# Snap2.net
KiCad netlist of a schematic drawn in Altium Designer
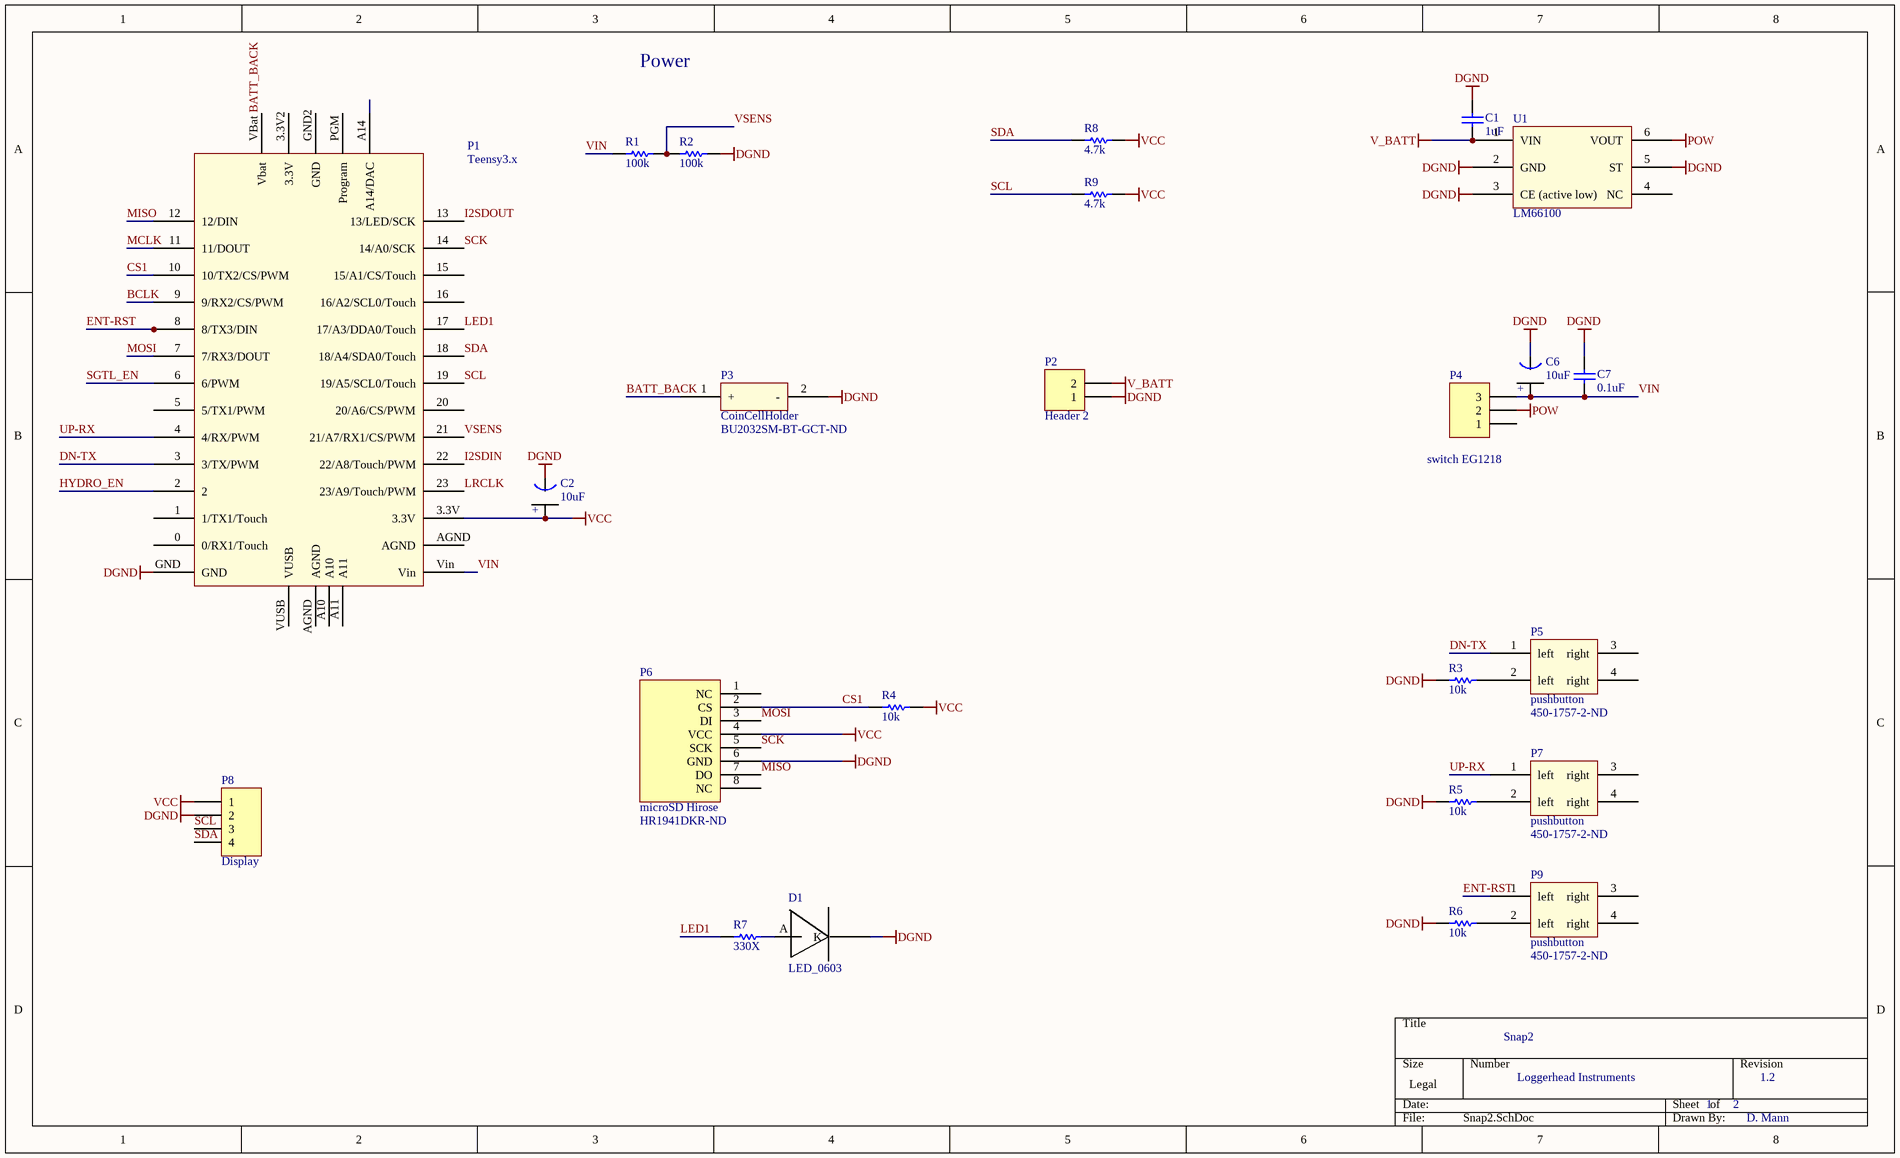
[diagram p0: Snap2.SchDoc]

(export (version "E")
  (design (tool "Eeschema 10.0.6"))
  (components
    (comp (ref "C1")
      (value "1uF")
      (footprint "0402")
      (description "Ceramic Chip Capacitor - Standard")
      (fields (field (name "PUBLISHER") "Altium Limited"))
      (libsource (lib "KEMET Chip Capacitor") (part "C0402"))
    )
    (comp (ref "C2") (value "10uF") (footprint "Tant0805") (libsource (lib "Loggerhead") (part "Tant0805")))
    (comp (ref "C6") (value "10uF") (footprint "Tant0805") (libsource (lib "Loggerhead") (part "Tant0805")))
    (comp (ref "C7")
      (value "0.1uF")
      (footprint "0402")
      (description "Ceramic Chip Capacitor - Standard")
      (fields (field (name "PUBLISHER") "Altium Limited"))
      (libsource (lib "KEMET Chip Capacitor") (part "C0402"))
    )
    (comp (ref "D1")
      (value "LED_0603")
      (footprint "Diode0603")
      (libsource (lib "Loggerhead") (part "LED_0603"))
    )
    (comp (ref "P1")
      (value "Teensy3.x")
      (footprint "Teensy3.x")
      (libsource (lib "Teensy") (part "Teensy3.x"))
    )
    (comp (ref "P2")
      (value "Header 2")
      (footprint "HDR1X2")
      (description "Header, 2-Pin")
      (fields (field (name "PUBLISHER") "Altium Limited"))
      (libsource (lib "Miscellaneous Connectors") (part "Header 2"))
    )
    (comp (ref "P3")
      (value "CoinCellHolder")
      (footprint "CoinCellHolder")
      (fields (field (name "SUPPLIER PART NUMBER 1") "BU2032SM-BT-GCT-ND"))
      (libsource (lib "Loggerhead") (part "CoinCellHolder"))
    )
    (comp (ref "P4")
      (value "switch EG1218")
      (footprint "HDR1X3")
      (description "Header, 3-Pin")
      (fields (field (name "PUBLISHER") "Altium Limited"))
      (libsource (lib "Miscellaneous Connectors") (part "Header 3"))
    )
    (comp (ref "P5")
      (value "pushbutton")
      (footprint "SOP4")
      (fields (field (name "SUPPLIER PART NUMBER 1") "450-1757-2-ND"))
      (libsource (lib "Loggerhead") (part "pushbutton"))
    )
    (comp (ref "P6")
      (value "microSD Hirose")
      (footprint "DM3D microSD")
      (fields (field (name "SUPPLIER PART NUMBER 1") "HR1941DKR-ND"))
      (libsource (lib "Loggerhead") (part "microSD Hirose"))
    )
    (comp (ref "P7")
      (value "pushbutton")
      (footprint "SOP4")
      (fields (field (name "SUPPLIER PART NUMBER 1") "450-1757-2-ND"))
      (libsource (lib "Loggerhead") (part "pushbutton"))
    )
    (comp (ref "P8")
      (value "Display")
      (footprint "HDR1X4")
      (description "Header, 4-Pin")
      (fields (field (name "PUBLISHER") "Altium Limited"))
      (libsource (lib "Miscellaneous Connectors") (part "Header 4"))
    )
    (comp (ref "P9")
      (value "pushbutton")
      (footprint "SOP4")
      (fields (field (name "SUPPLIER PART NUMBER 1") "450-1757-2-ND"))
      (libsource (lib "Loggerhead") (part "pushbutton"))
    )
    (comp (ref "R1")
      (value "100k")
      (footprint "3-0603")
      (fields (field (name "PUBLISHER") "Altium Limited"))
      (libsource (lib "Panasonic Resistor") (part "ERJ3RK"))
    )
    (comp (ref "R2")
      (value "100k")
      (footprint "3-0603")
      (fields (field (name "PUBLISHER") "Altium Limited"))
      (libsource (lib "Panasonic Resistor") (part "ERJ3RK"))
    )
    (comp (ref "R3")
      (value "10k")
      (footprint "3-0603")
      (fields (field (name "PUBLISHER") "Altium Limited"))
      (libsource (lib "Panasonic Resistor") (part "ERJ3RK"))
    )
    (comp (ref "R4")
      (value "10k")
      (footprint "3-0603")
      (fields (field (name "PUBLISHER") "Altium Limited"))
      (libsource (lib "Panasonic Resistor") (part "ERJ3RK"))
    )
    (comp (ref "R5")
      (value "10k")
      (footprint "3-0603")
      (fields (field (name "PUBLISHER") "Altium Limited"))
      (libsource (lib "Panasonic Resistor") (part "ERJ3RK"))
    )
    (comp (ref "R6")
      (value "10k")
      (footprint "3-0603")
      (fields (field (name "PUBLISHER") "Altium Limited"))
      (libsource (lib "Panasonic Resistor") (part "ERJ3RK"))
    )
    (comp (ref "R7")
      (value "330X")
      (footprint "3-0603")
      (fields (field (name "PUBLISHER") "Altium Limited"))
      (libsource (lib "Panasonic Resistor") (part "ERJ3RK"))
    )
    (comp (ref "R8")
      (value "4.7k")
      (footprint "3-0603")
      (fields (field (name "PUBLISHER") "Altium Limited"))
      (libsource (lib "Panasonic Resistor") (part "ERJ3RK"))
    )
    (comp (ref "R9")
      (value "4.7k")
      (footprint "3-0603")
      (fields (field (name "PUBLISHER") "Altium Limited"))
      (libsource (lib "Panasonic Resistor") (part "ERJ3RK"))
    )
    (comp (ref "U1") (value "LM66100") (footprint "SC-70-6") (libsource (lib "Loggerhead") (part "LM66100")))
  )
  (nets
    (net (code "1") (name "/BATT_BACK") (class "Default")
      (node (ref "P1") (pin "VBat") (pinfunction "Vbat_VBat") (pintype "passive"))
      (node (ref "P3") (pin "1") (pinfunction "+_1") (pintype "passive"))
    )
    (net (code "2") (name "/BCLK") (class "Default")
      (node (ref "P1") (pin "9") (pinfunction "9/RX2/CS/PWM_9") (pintype "passive"))
    )
    (net (code "3") (name "/CS1") (class "Default")
      (node (ref "P1") (pin "10") (pinfunction "10/TX2/CS/PWM_10") (pintype "passive"))
      (node (ref "P6") (pin "2") (pinfunction "CS_2") (pintype "passive"))
      (node (ref "R4") (pin "2") (pinfunction "2_2") (pintype "passive"))
    )
    (net (code "4") (name "/DN-TX") (class "Default")
      (node (ref "P1") (pin "3") (pinfunction "3/TX/PWM_3") (pintype "passive"))
      (node (ref "P5") (pin "1") (pinfunction "left_1") (pintype "passive"))
    )
    (net (code "5") (name "/ENT-RST") (class "Default")
      (node (ref "P1") (pin "8") (pinfunction "8/TX3/DIN_8") (pintype "passive"))
      (node (ref "P9") (pin "1") (pinfunction "left_1") (pintype "passive"))
    )
    (net (code "6") (name "/HYDRO_EN") (class "Default")
      (node (ref "P1") (pin "2") (pinfunction "2_2") (pintype "passive"))
    )
    (net (code "7") (name "/I2SDIN") (class "Default")
      (node (ref "P1") (pin "22") (pinfunction "22/A8/Touch/PWM_22") (pintype "passive"))
    )
    (net (code "8") (name "/I2SDOUT") (class "Default")
      (node (ref "P1") (pin "13") (pinfunction "13/LED/SCK_13") (pintype "passive"))
    )
    (net (code "9") (name "/LED1") (class "Default")
      (node (ref "P1") (pin "17") (pinfunction "17/A3/DDA0/Touch_17") (pintype "passive"))
      (node (ref "R7") (pin "1") (pinfunction "1_1") (pintype "passive"))
    )
    (net (code "10") (name "/LRCLK") (class "Default")
      (node (ref "P1") (pin "23") (pinfunction "23/A9/Touch/PWM_23") (pintype "passive"))
    )
    (net (code "11") (name "/MCLK") (class "Default")
      (node (ref "P1") (pin "11") (pinfunction "11/DOUT_11") (pintype "passive"))
    )
    (net (code "12") (name "/MISO") (class "Default")
      (node (ref "P1") (pin "12") (pinfunction "12/DIN_12") (pintype "passive"))
      (node (ref "P6") (pin "7") (pinfunction "DO_7") (pintype "passive"))
    )
    (net (code "13") (name "/MOSI") (class "Default")
      (node (ref "P1") (pin "7") (pinfunction "7/RX3/DOUT_7") (pintype "passive"))
      (node (ref "P6") (pin "3") (pinfunction "DI_3") (pintype "passive"))
    )
    (net (code "14") (name "/SCK") (class "Default")
      (node (ref "P1") (pin "14") (pinfunction "14/A0/SCK_14") (pintype "passive"))
      (node (ref "P6") (pin "5") (pinfunction "SCK_5") (pintype "passive"))
    )
    (net (code "15") (name "/SCL") (class "Default")
      (node (ref "P1") (pin "19") (pinfunction "19/A5/SCL0/Touch_19") (pintype "passive"))
      (node (ref "P8") (pin "3") (pinfunction "3_3") (pintype "passive"))
      (node (ref "R9") (pin "1") (pinfunction "1_1") (pintype "passive"))
    )
    (net (code "16") (name "/SDA") (class "Default")
      (node (ref "P1") (pin "18") (pinfunction "18/A4/SDA0/Touch_18") (pintype "passive"))
      (node (ref "P8") (pin "4") (pinfunction "4_4") (pintype "passive"))
      (node (ref "R8") (pin "1") (pinfunction "1_1") (pintype "passive"))
    )
    (net (code "17") (name "/SGTL_EN") (class "Default")
      (node (ref "P1") (pin "6") (pinfunction "6/PWM_6") (pintype "passive"))
    )
    (net (code "18") (name "/UP-RX") (class "Default")
      (node (ref "P1") (pin "4") (pinfunction "4/RX/PWM_4") (pintype "passive"))
      (node (ref "P7") (pin "1") (pinfunction "left_1") (pintype "passive"))
    )
    (net (code "19") (name "/VIN") (class "Default")
      (node (ref "C6") (pin "2") (pinfunction "+_2") (pintype "passive"))
      (node (ref "C7") (pin "1") (pinfunction "1_1") (pintype "passive"))
      (node (ref "P1") (pin "Vin") (pinfunction "Vin_Vin") (pintype "passive"))
      (node (ref "P4") (pin "3") (pinfunction "3_3") (pintype "passive"))
      (node (ref "R1") (pin "2") (pinfunction "2_2") (pintype "passive"))
    )
    (net (code "20") (name "/VSENS") (class "Default")
      (node (ref "P1") (pin "21") (pinfunction "21/A7/RX1/CS/PWM_21") (pintype "passive"))
      (node (ref "R1") (pin "1") (pinfunction "1_1") (pintype "passive"))
      (node (ref "R2") (pin "2") (pinfunction "2_2") (pintype "passive"))
    )
    (net (code "21") (name "DGND") (class "Default")
      (node (ref "C1") (pin "1") (pinfunction "1_1") (pintype "passive"))
      (node (ref "C2") (pin "1") (pinfunction "GND_1") (pintype "passive"))
      (node (ref "C6") (pin "1") (pinfunction "GND_1") (pintype "passive"))
      (node (ref "C7") (pin "2") (pinfunction "2_2") (pintype "passive"))
      (node (ref "D1") (pin "K") (pinfunction "K_K") (pintype "passive"))
      (node (ref "P1") (pin "GND") (pinfunction "GND_GND") (pintype "passive"))
      (node (ref "P2") (pin "1") (pinfunction "1_1") (pintype "passive"))
      (node (ref "P3") (pin "2") (pinfunction "-_2") (pintype "passive"))
      (node (ref "P6") (pin "6") (pinfunction "GND_6") (pintype "passive"))
      (node (ref "P8") (pin "2") (pinfunction "2_2") (pintype "passive"))
      (node (ref "R2") (pin "1") (pinfunction "1_1") (pintype "passive"))
      (node (ref "R3") (pin "2") (pinfunction "2_2") (pintype "passive"))
      (node (ref "R5") (pin "2") (pinfunction "2_2") (pintype "passive"))
      (node (ref "R6") (pin "2") (pinfunction "2_2") (pintype "passive"))
      (node (ref "U1") (pin "2") (pinfunction "GND_2") (pintype "passive"))
      (node (ref "U1") (pin "3") (pinfunction "CE_(active_low)_3") (pintype "passive"))
      (node (ref "U1") (pin "5") (pinfunction "ST_5") (pintype "passive"))
    )
    (net (code "22") (name "Net-(D1-PadA)") (class "Default")
      (node (ref "D1") (pin "A") (pinfunction "A_A") (pintype "passive"))
      (node (ref "R7") (pin "2") (pinfunction "2_2") (pintype "passive"))
    )
    (net (code "23") (name "Net-(P5-left-Pad2)") (class "Default")
      (node (ref "P5") (pin "2") (pinfunction "left_2") (pintype "passive"))
      (node (ref "R3") (pin "1") (pinfunction "1_1") (pintype "passive"))
    )
    (net (code "24") (name "Net-(P7-left-Pad2)") (class "Default")
      (node (ref "P7") (pin "2") (pinfunction "left_2") (pintype "passive"))
      (node (ref "R5") (pin "1") (pinfunction "1_1") (pintype "passive"))
    )
    (net (code "25") (name "Net-(P9-left-Pad2)") (class "Default")
      (node (ref "P9") (pin "2") (pinfunction "left_2") (pintype "passive"))
      (node (ref "R6") (pin "1") (pinfunction "1_1") (pintype "passive"))
    )
    (net (code "26") (name "POW") (class "Default")
      (node (ref "P4") (pin "2") (pinfunction "2_2") (pintype "passive"))
      (node (ref "U1") (pin "6") (pinfunction "VOUT_6") (pintype "passive"))
    )
    (net (code "27") (name "VCC") (class "Default")
      (node (ref "C2") (pin "2") (pinfunction "+_2") (pintype "passive"))
      (node (ref "P1") (pin "3.3V") (pinfunction "3.3V_3.3V") (pintype "passive"))
      (node (ref "P6") (pin "4") (pinfunction "VCC_4") (pintype "passive"))
      (node (ref "P8") (pin "1") (pinfunction "1_1") (pintype "passive"))
      (node (ref "R4") (pin "1") (pinfunction "1_1") (pintype "passive"))
      (node (ref "R8") (pin "2") (pinfunction "2_2") (pintype "passive"))
      (node (ref "R9") (pin "2") (pinfunction "2_2") (pintype "passive"))
    )
    (net (code "28") (name "V_BATT") (class "Default")
      (node (ref "C1") (pin "2") (pinfunction "2_2") (pintype "passive"))
      (node (ref "P2") (pin "2") (pinfunction "2_2") (pintype "passive"))
      (node (ref "U1") (pin "1") (pinfunction "VIN_1") (pintype "passive"))
    )
    (net (code "29") (name "unconnected-(P1-0{slash}RX1{slash}Touch-Pad0)") (class "Default")
      (node (ref "P1") (pin "0") (pinfunction "0/RX1/Touch_0") (pintype "passive"))
    )
    (net (code "30") (name "unconnected-(P1-1{slash}TX1{slash}Touch-Pad1)") (class "Default")
      (node (ref "P1") (pin "1") (pinfunction "1/TX1/Touch_1") (pintype "passive"))
    )
    (net (code "31") (name "unconnected-(P1-3.3V-Pad3.3V2)") (class "Default")
      (node (ref "P1") (pin "3.3V2") (pinfunction "3.3V_3.3V2") (pintype "passive"))
    )
    (net (code "32") (name "unconnected-(P1-5{slash}TX1{slash}PWM-Pad5)") (class "Default")
      (node (ref "P1") (pin "5") (pinfunction "5/TX1/PWM_5") (pintype "passive"))
    )
    (net (code "33") (name "unconnected-(P1-15{slash}A1{slash}CS{slash}Touch-Pad15)") (class "Default")
      (node (ref "P1") (pin "15") (pinfunction "15/A1/CS/Touch_15") (pintype "passive"))
    )
    (net (code "34") (name "unconnected-(P1-16{slash}A2{slash}SCL0{slash}Touch-Pad16)") (class "Default")
      (node (ref "P1") (pin "16") (pinfunction "16/A2/SCL0/Touch_16") (pintype "passive"))
    )
    (net (code "35") (name "unconnected-(P1-20{slash}A6{slash}CS{slash}PWM-Pad20)") (class "Default")
      (node (ref "P1") (pin "20") (pinfunction "20/A6/CS/PWM_20") (pintype "passive"))
    )
    (net (code "36") (name "unconnected-(P1-A14{slash}DAC-PadA14)") (class "Default")
      (node (ref "P1") (pin "A14") (pinfunction "A14/DAC_A14") (pintype "passive"))
    )
    (net (code "37") (name "unconnected-(P1-GND-PadGND2)") (class "Default")
      (node (ref "P1") (pin "GND2") (pinfunction "GND_GND2") (pintype "passive"))
    )
    (net (code "38") (name "unconnected-(P1-PadA10)") (class "Default")
      (node (ref "P1") (pin "A10") (pinfunction "A10_A10") (pintype "passive"))
    )
    (net (code "39") (name "unconnected-(P1-PadA11)") (class "Default")
      (node (ref "P1") (pin "A11") (pinfunction "A11_A11") (pintype "passive"))
    )
    (net (code "40") (name "unconnected-(P1-PadAGND)") (class "Default")
      (node (ref "P1") (pin "AGND") (pinfunction "AGND_AGND") (pintype "passive"))
    )
    (net (code "41") (name "unconnected-(P1-PadAGND)_1") (class "Default")
      (node (ref "P1") (pin "AGND") (pinfunction "AGND_AGND") (pintype "passive"))
    )
    (net (code "42") (name "unconnected-(P1-PadVUSB)") (class "Default")
      (node (ref "P1") (pin "VUSB") (pinfunction "VUSB_VUSB") (pintype "passive"))
    )
    (net (code "43") (name "unconnected-(P1-Program-PadPGM)") (class "Default")
      (node (ref "P1") (pin "PGM") (pinfunction "Program_PGM") (pintype "passive"))
    )
    (net (code "44") (name "unconnected-(P4-Pad1)") (class "Default")
      (node (ref "P4") (pin "1") (pinfunction "1_1") (pintype "passive"))
    )
    (net (code "45") (name "unconnected-(P5-right-Pad3)") (class "Default")
      (node (ref "P5") (pin "3") (pinfunction "right_3") (pintype "passive"))
    )
    (net (code "46") (name "unconnected-(P5-right-Pad4)") (class "Default")
      (node (ref "P5") (pin "4") (pinfunction "right_4") (pintype "passive"))
    )
    (net (code "47") (name "unconnected-(P6-NC-Pad1)") (class "Default")
      (node (ref "P6") (pin "1") (pinfunction "NC_1") (pintype "passive"))
    )
    (net (code "48") (name "unconnected-(P6-NC-Pad8)") (class "Default")
      (node (ref "P6") (pin "8") (pinfunction "NC_8") (pintype "passive"))
    )
    (net (code "49") (name "unconnected-(P7-right-Pad3)") (class "Default")
      (node (ref "P7") (pin "3") (pinfunction "right_3") (pintype "passive"))
    )
    (net (code "50") (name "unconnected-(P7-right-Pad4)") (class "Default")
      (node (ref "P7") (pin "4") (pinfunction "right_4") (pintype "passive"))
    )
    (net (code "51") (name "unconnected-(P9-right-Pad3)") (class "Default")
      (node (ref "P9") (pin "3") (pinfunction "right_3") (pintype "passive"))
    )
    (net (code "52") (name "unconnected-(P9-right-Pad4)") (class "Default")
      (node (ref "P9") (pin "4") (pinfunction "right_4") (pintype "passive"))
    )
    (net (code "53") (name "unconnected-(U1-NC-Pad4)") (class "Default")
      (node (ref "U1") (pin "4") (pinfunction "NC_4") (pintype "passive"))
    )
  )
)
